# Trabajo4.net
KiCad netlist of a schematic drawn in EAGLE
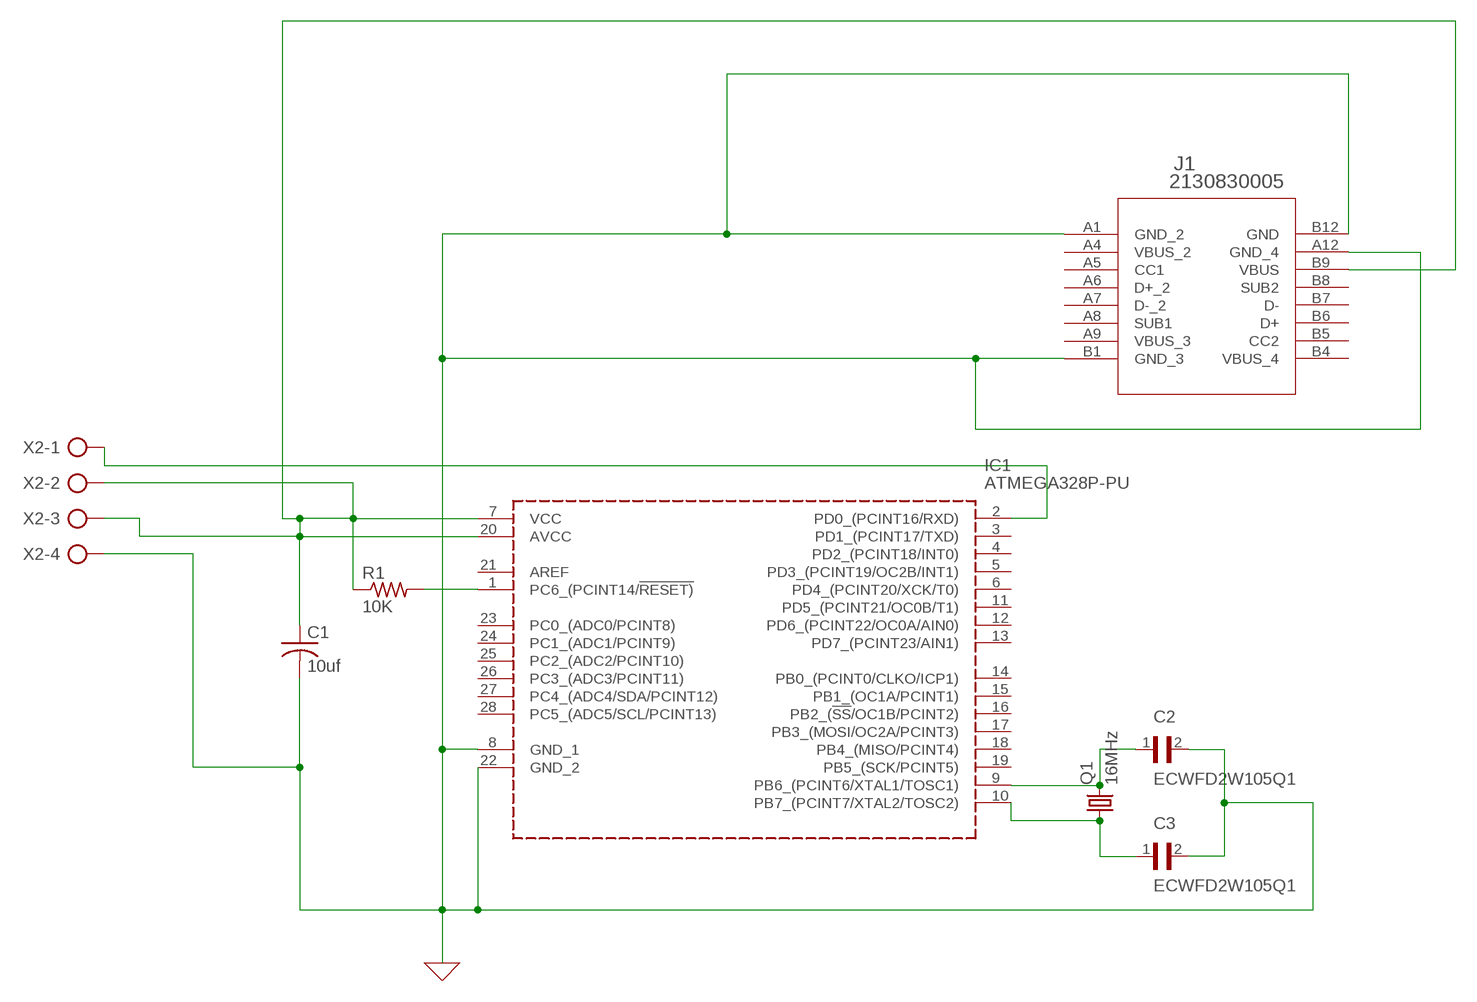
[diagram p0: schematic, sheet 1]

(export (version "E")
  (design (tool "Eeschema 10.0.6"))
  (components
    (comp (ref "C1")
      (value "10uf")
      (footprint "eagle-import:C025-024X044")
      (fields (field (name "POPULARITY") "10Uf"))
      (libsource (lib "eagle-import") (part "C-US025-024X044"))
    )
    (comp (ref "C2")
      (value "ECWFD2W105Q1")
      (footprint "eagle-import:CAPRR1000W60L1260T920H1390")
      (fields (field (name "MF") "Panasonic"))
      (libsource (lib "eagle-import") (part "ECWFD2W105Q1"))
    )
    (comp (ref "C3")
      (value "ECWFD2W105Q1")
      (footprint "eagle-import:CAPRR1000W60L1260T920H1390")
      (fields (field (name "MF") "Panasonic"))
      (libsource (lib "eagle-import") (part "ECWFD2W105Q1"))
    )
    (comp (ref "IC1")
      (value "ATMEGA328P-PU")
      (footprint "eagle-import:DIP794W53P254L3467H457Q28N")
      (fields (field (name "MF") "Microchip Technology") (field (name "MP") "ATMEGA328PPU"))
      (libsource (lib "eagle-import") (part "ATMEGA328P-PU"))
    )
    (comp (ref "J1")
      (value "2130830005")
      (footprint "eagle-import:2130830005_MOL")
      (fields (field (name "MF") "Molex"))
      (libsource (lib "eagle-import") (part "2130830005"))
    )
    (comp (ref "Q1")
      (value "16MHz")
      (footprint "eagle-import:HC33U-V")
      (libsource (lib "eagle-import") (part "CRYSTALHC33U-V"))
    )
    (comp (ref "R1")
      (value "10K")
      (footprint "eagle-import:0204V")
      (fields (field (name "POPULARITY") "10k"))
      (libsource (lib "eagle-import") (part "R-US_0204/2V"))
    )
    (comp (ref "X2")
      (value "AK500/4-H")
      (footprint "eagle-import:AK500_4-H")
      (libsource (lib "eagle-import") (part "AK500/4-H"))
    )
  )
  (nets
    (net (code "1") (name "/VBUS_2") (class "Default")
      (node (ref "J1") (pin "A4") (pinfunction "VBUS_2_A4") (pintype "power_in"))
    )
    (net (code "2") (name "/VBUS_3") (class "Default")
      (node (ref "J1") (pin "A9") (pinfunction "VBUS_3_A9") (pintype "power_in"))
    )
    (net (code "3") (name "/VBUS_4") (class "Default")
      (node (ref "J1") (pin "B4") (pinfunction "VBUS_4_B4") (pintype "power_in"))
    )
    (net (code "4") (name "GND") (class "Default")
      (node (ref "C1") (pin "2") (pinfunction "2_2") (pintype "passive"))
      (node (ref "C2") (pin "2") (pinfunction "2_2") (pintype "passive"))
      (node (ref "C3") (pin "2") (pinfunction "2_2") (pintype "passive"))
      (node (ref "IC1") (pin "22") (pinfunction "GND_2_22") (pintype "bidirectional"))
      (node (ref "IC1") (pin "8") (pinfunction "GND_1_8") (pintype "bidirectional"))
      (node (ref "J1") (pin "A1") (pinfunction "GND_2_A1") (pintype "passive"))
      (node (ref "J1") (pin "A12") (pinfunction "GND_4_A12") (pintype "passive"))
      (node (ref "J1") (pin "B1") (pinfunction "GND_3_B1") (pintype "passive"))
      (node (ref "J1") (pin "B12") (pinfunction "GND_B12") (pintype "passive"))
      (node (ref "X2") (pin "4") (pinfunction "KL_4") (pintype "passive"))
    )
    (net (code "5") (name "Net-(IC1-AVCC)") (class "Default")
      (node (ref "C1") (pin "1") (pinfunction "1_1") (pintype "passive"))
      (node (ref "IC1") (pin "20") (pinfunction "AVCC_20") (pintype "bidirectional"))
      (node (ref "IC1") (pin "7") (pinfunction "VCC_7") (pintype "bidirectional"))
      (node (ref "J1") (pin "B9") (pinfunction "VBUS_B9") (pintype "power_in"))
      (node (ref "R1") (pin "1") (pinfunction "1_1") (pintype "passive"))
      (node (ref "X2") (pin "2") (pinfunction "KL_2") (pintype "passive"))
      (node (ref "X2") (pin "3") (pinfunction "KL_3") (pintype "passive"))
    )
    (net (code "6") (name "Net-(IC1-PB6_(PCINT6{slash}XTAL1{slash}TOSC1))") (class "Default")
      (node (ref "C2") (pin "1") (pinfunction "1_1") (pintype "passive"))
      (node (ref "IC1") (pin "9") (pinfunction "PB6_(PCINT6/XTAL1/TOSC1)_9") (pintype "bidirectional"))
      (node (ref "Q1") (pin "2") (pinfunction "2_2") (pintype "passive"))
    )
    (net (code "7") (name "Net-(IC1-PB7_(PCINT7{slash}XTAL2{slash}TOSC2))") (class "Default")
      (node (ref "C3") (pin "1") (pinfunction "1_1") (pintype "passive"))
      (node (ref "IC1") (pin "10") (pinfunction "PB7_(PCINT7/XTAL2/TOSC2)_10") (pintype "bidirectional"))
      (node (ref "Q1") (pin "1") (pinfunction "1_1") (pintype "passive"))
    )
    (net (code "8") (name "Net-(IC1-PC6_(PCINT14{slash}~{RESET}))") (class "Default")
      (node (ref "IC1") (pin "1") (pinfunction "PC6_(PCINT14/~{RESET})_1") (pintype "bidirectional"))
      (node (ref "R1") (pin "2") (pinfunction "2_2") (pintype "passive"))
    )
    (net (code "9") (name "Net-(IC1-PD0_(PCINT16{slash}RXD))") (class "Default")
      (node (ref "IC1") (pin "2") (pinfunction "PD0_(PCINT16/RXD)_2") (pintype "bidirectional"))
      (node (ref "X2") (pin "1") (pinfunction "KL_1") (pintype "passive"))
    )
    (net (code "10") (name "unconnected-(IC1-AREF-Pad21)") (class "Default")
      (node (ref "IC1") (pin "21") (pinfunction "AREF_21") (pintype "bidirectional"))
    )
    (net (code "11") (name "unconnected-(IC1-PB0_(PCINT0{slash}CLKO{slash}ICP1)-Pad14)") (class "Default")
      (node (ref "IC1") (pin "14") (pinfunction "PB0_(PCINT0/CLKO/ICP1)_14") (pintype "bidirectional"))
    )
    (net (code "12") (name "unconnected-(IC1-PB1_(OC1A{slash}PCINT1)-Pad15)") (class "Default")
      (node (ref "IC1") (pin "15") (pinfunction "PB1_(OC1A/PCINT1)_15") (pintype "bidirectional"))
    )
    (net (code "13") (name "unconnected-(IC1-PB2_(~{SS}{slash}OC1B{slash}PCINT2)-Pad16)") (class "Default")
      (node (ref "IC1") (pin "16") (pinfunction "PB2_(~{SS}/OC1B/PCINT2)_16") (pintype "bidirectional"))
    )
    (net (code "14") (name "unconnected-(IC1-PB3_(MOSI{slash}OC2A{slash}PCINT3)-Pad17)") (class "Default")
      (node (ref "IC1") (pin "17") (pinfunction "PB3_(MOSI/OC2A/PCINT3)_17") (pintype "bidirectional"))
    )
    (net (code "15") (name "unconnected-(IC1-PB4_(MISO{slash}PCINT4)-Pad18)") (class "Default")
      (node (ref "IC1") (pin "18") (pinfunction "PB4_(MISO/PCINT4)_18") (pintype "bidirectional"))
    )
    (net (code "16") (name "unconnected-(IC1-PB5_(SCK{slash}PCINT5)-Pad19)") (class "Default")
      (node (ref "IC1") (pin "19") (pinfunction "PB5_(SCK/PCINT5)_19") (pintype "bidirectional"))
    )
    (net (code "17") (name "unconnected-(IC1-PC0_(ADC0{slash}PCINT8)-Pad23)") (class "Default")
      (node (ref "IC1") (pin "23") (pinfunction "PC0_(ADC0/PCINT8)_23") (pintype "bidirectional"))
    )
    (net (code "18") (name "unconnected-(IC1-PC1_(ADC1{slash}PCINT9)-Pad24)") (class "Default")
      (node (ref "IC1") (pin "24") (pinfunction "PC1_(ADC1/PCINT9)_24") (pintype "bidirectional"))
    )
    (net (code "19") (name "unconnected-(IC1-PC2_(ADC2{slash}PCINT10)-Pad25)") (class "Default")
      (node (ref "IC1") (pin "25") (pinfunction "PC2_(ADC2/PCINT10)_25") (pintype "bidirectional"))
    )
    (net (code "20") (name "unconnected-(IC1-PC3_(ADC3{slash}PCINT11)-Pad26)") (class "Default")
      (node (ref "IC1") (pin "26") (pinfunction "PC3_(ADC3/PCINT11)_26") (pintype "bidirectional"))
    )
    (net (code "21") (name "unconnected-(IC1-PC4_(ADC4{slash}SDA{slash}PCINT12)-Pad27)") (class "Default")
      (node (ref "IC1") (pin "27") (pinfunction "PC4_(ADC4/SDA/PCINT12)_27") (pintype "bidirectional"))
    )
    (net (code "22") (name "unconnected-(IC1-PC5_(ADC5{slash}SCL{slash}PCINT13)-Pad28)") (class "Default")
      (node (ref "IC1") (pin "28") (pinfunction "PC5_(ADC5/SCL/PCINT13)_28") (pintype "bidirectional"))
    )
    (net (code "23") (name "unconnected-(IC1-PD1_(PCINT17{slash}TXD)-Pad3)") (class "Default")
      (node (ref "IC1") (pin "3") (pinfunction "PD1_(PCINT17/TXD)_3") (pintype "bidirectional"))
    )
    (net (code "24") (name "unconnected-(IC1-PD2_(PCINT18{slash}INT0)-Pad4)") (class "Default")
      (node (ref "IC1") (pin "4") (pinfunction "PD2_(PCINT18/INT0)_4") (pintype "bidirectional"))
    )
    (net (code "25") (name "unconnected-(IC1-PD3_(PCINT19{slash}OC2B{slash}INT1)-Pad5)") (class "Default")
      (node (ref "IC1") (pin "5") (pinfunction "PD3_(PCINT19/OC2B/INT1)_5") (pintype "bidirectional"))
    )
    (net (code "26") (name "unconnected-(IC1-PD4_(PCINT20{slash}XCK{slash}T0)-Pad6)") (class "Default")
      (node (ref "IC1") (pin "6") (pinfunction "PD4_(PCINT20/XCK/T0)_6") (pintype "bidirectional"))
    )
    (net (code "27") (name "unconnected-(IC1-PD5_(PCINT21{slash}OC0B{slash}T1)-Pad11)") (class "Default")
      (node (ref "IC1") (pin "11") (pinfunction "PD5_(PCINT21/OC0B/T1)_11") (pintype "bidirectional"))
    )
    (net (code "28") (name "unconnected-(IC1-PD6_(PCINT22{slash}OC0A{slash}AIN0)-Pad12)") (class "Default")
      (node (ref "IC1") (pin "12") (pinfunction "PD6_(PCINT22/OC0A/AIN0)_12") (pintype "bidirectional"))
    )
    (net (code "29") (name "unconnected-(IC1-PD7_(PCINT23{slash}AIN1)-Pad13)") (class "Default")
      (node (ref "IC1") (pin "13") (pinfunction "PD7_(PCINT23/AIN1)_13") (pintype "bidirectional"))
    )
    (net (code "30") (name "unconnected-(J1-CC1-PadA5)") (class "Default")
      (node (ref "J1") (pin "A5") (pinfunction "CC1_A5") (pintype "bidirectional"))
    )
    (net (code "31") (name "unconnected-(J1-CC2-PadB5)") (class "Default")
      (node (ref "J1") (pin "B5") (pinfunction "CC2_B5") (pintype "bidirectional"))
    )
    (net (code "32") (name "unconnected-(J1-D+-PadB6)") (class "Default")
      (node (ref "J1") (pin "B6") (pinfunction "D+_B6") (pintype "bidirectional"))
    )
    (net (code "33") (name "unconnected-(J1-D+_2-PadA6)") (class "Default")
      (node (ref "J1") (pin "A6") (pinfunction "D+_2_A6") (pintype "bidirectional"))
    )
    (net (code "34") (name "unconnected-(J1-D--PadB7)") (class "Default")
      (node (ref "J1") (pin "B7") (pinfunction "D-_B7") (pintype "bidirectional"))
    )
    (net (code "35") (name "unconnected-(J1-D-_2-PadA7)") (class "Default")
      (node (ref "J1") (pin "A7") (pinfunction "D-_2_A7") (pintype "bidirectional"))
    )
    (net (code "36") (name "unconnected-(J1-SUB1-PadA8)") (class "Default")
      (node (ref "J1") (pin "A8") (pinfunction "SUB1_A8") (pintype "bidirectional"))
    )
    (net (code "37") (name "unconnected-(J1-SUB2-PadB8)") (class "Default")
      (node (ref "J1") (pin "B8") (pinfunction "SUB2_B8") (pintype "bidirectional"))
    )
  )
)
